# IHM.net
KiCad netlist of a schematic drawn in Altium Designer
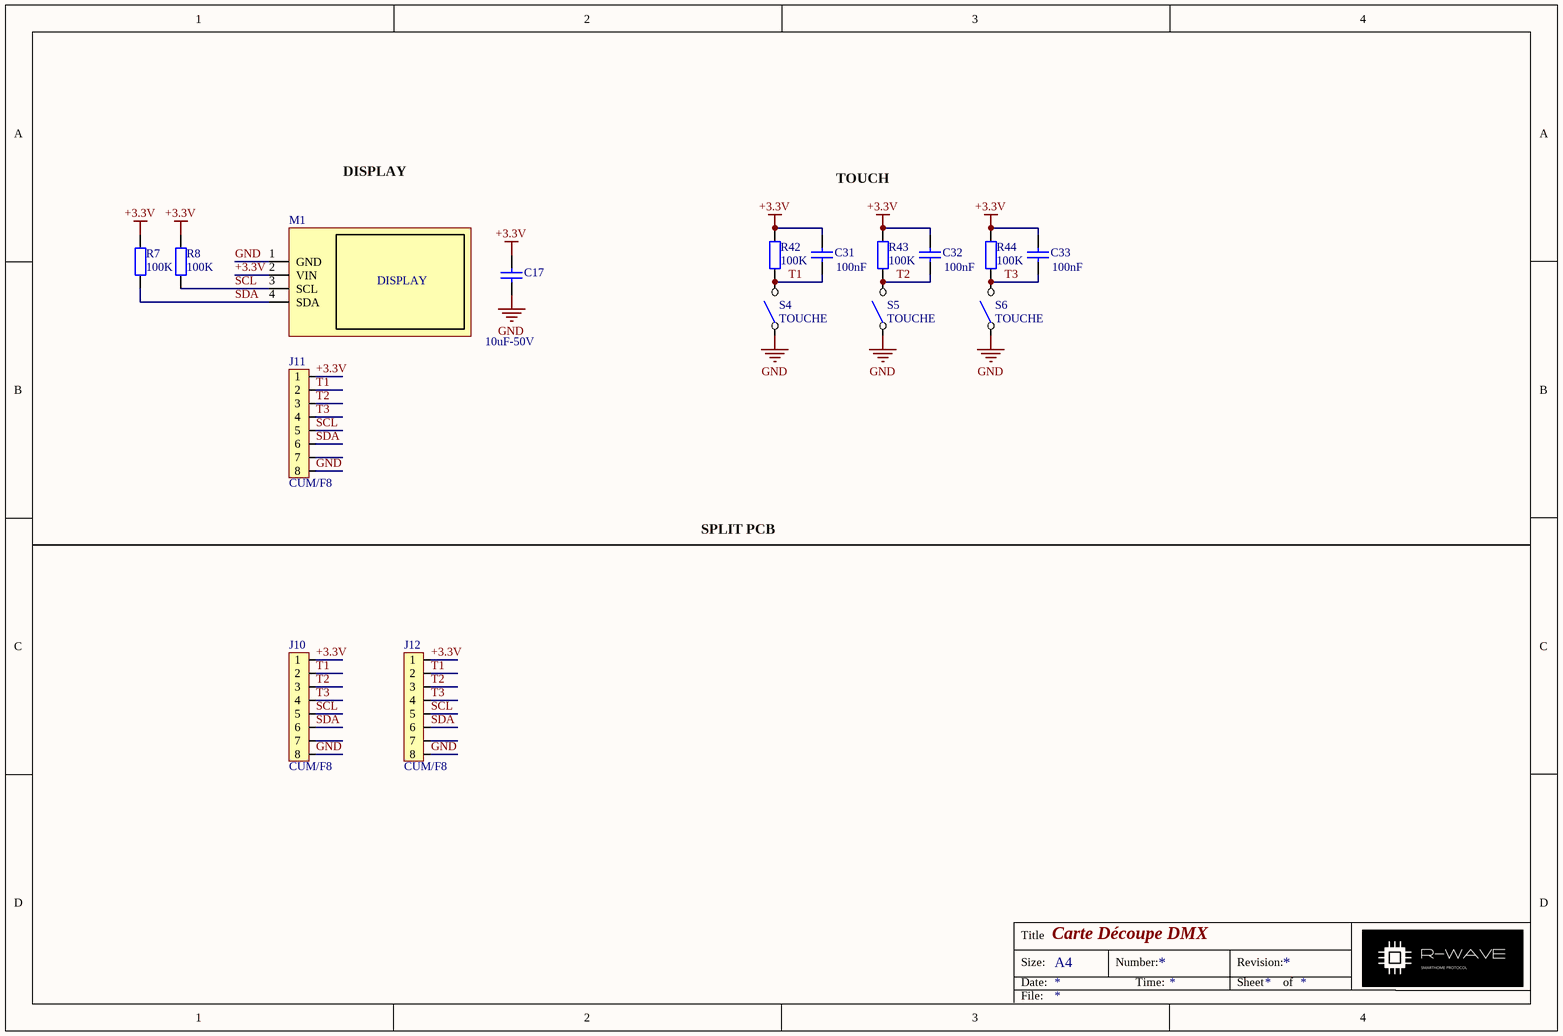
[diagram p0: IHM.SchDoc]

(export (version "E")
  (design (tool "Eeschema 10.0.6"))
  (components
    (comp (ref "C17")
      (value "10uF-50V")
      (footprint "C1206")
      (description "Capacitor")
      (libsource (lib "MyLibrary") (part "Cap"))
    )
    (comp (ref "C31")
      (value "100nF")
      (footprint "C0603")
      (description "Capacitor")
      (libsource (lib "MyLibrary") (part "Cap"))
    )
    (comp (ref "C32")
      (value "100nF")
      (footprint "C0603")
      (description "Capacitor")
      (libsource (lib "MyLibrary") (part "Cap"))
    )
    (comp (ref "C33")
      (value "100nF")
      (footprint "C0603")
      (description "Capacitor")
      (libsource (lib "MyLibrary") (part "Cap"))
    )
    (comp (ref "J10")
      (value "CUM/F8")
      (footprint "BARF-2X4")
      (description "connecteur 8 points")
      (libsource (lib "PROTEL") (part "CUM/F8"))
    )
    (comp (ref "J11")
      (value "CUM/F8")
      (footprint "BARF-2X4")
      (description "connecteur 8 points")
      (libsource (lib "PROTEL") (part "CUM/F8"))
    )
    (comp (ref "J12")
      (value "CUM/F8")
      (footprint "BARF-2X4")
      (description "connecteur 8 points")
      (libsource (lib "PROTEL") (part "CUM/F8"))
    )
    (comp (ref "M1")
      (value "~")
      (footprint "I2C_OLED_0.96")
      (description "I2C OLED 0.96\"")
      (libsource (lib "MyLibrary") (part "I2C-OLED-0.96"))
    )
    (comp (ref "R7")
      (value "100K")
      (footprint "R0603")
      (description "Thin Metal Film Resistor")
      (libsource (lib "MyLibrary") (part "Res"))
    )
    (comp (ref "R8")
      (value "100K")
      (footprint "R0603")
      (description "Thin Metal Film Resistor")
      (libsource (lib "MyLibrary") (part "Res"))
    )
    (comp (ref "R42")
      (value "100K")
      (footprint "R0603")
      (description "Thin Metal Film Resistor")
      (libsource (lib "MyLibrary") (part "Res"))
    )
    (comp (ref "R43")
      (value "100K")
      (footprint "R0603")
      (description "Thin Metal Film Resistor")
      (libsource (lib "MyLibrary") (part "Res"))
    )
    (comp (ref "R44")
      (value "100K")
      (footprint "R0603")
      (description "Thin Metal Film Resistor")
      (libsource (lib "MyLibrary") (part "Res"))
    )
    (comp (ref "S4")
      (value "TOUCHE")
      (footprint "INT-O")
      (description "Touche")
      (libsource (lib "PROTEL") (part "TOUCHE"))
    )
    (comp (ref "S5")
      (value "TOUCHE")
      (footprint "INT-O")
      (description "Touche")
      (libsource (lib "PROTEL") (part "TOUCHE"))
    )
    (comp (ref "S6")
      (value "TOUCHE")
      (footprint "INT-O")
      (description "Touche")
      (libsource (lib "PROTEL") (part "TOUCHE"))
    )
  )
  (nets
    (net (code "1") (name "+3.3V") (class "Default")
      (node (ref "C17") (pin "2") (pinfunction "2_2") (pintype "passive"))
      (node (ref "C31") (pin "2") (pinfunction "2_2") (pintype "passive"))
      (node (ref "C32") (pin "2") (pinfunction "2_2") (pintype "passive"))
      (node (ref "C33") (pin "2") (pinfunction "2_2") (pintype "passive"))
      (node (ref "J10") (pin "1") (pinfunction "1_1") (pintype "passive"))
      (node (ref "J11") (pin "1") (pinfunction "1_1") (pintype "passive"))
      (node (ref "J12") (pin "1") (pinfunction "1_1") (pintype "passive"))
      (node (ref "M1") (pin "2") (pinfunction "VIN_2") (pintype "power_in"))
      (node (ref "R42") (pin "2") (pinfunction "2_2") (pintype "passive"))
      (node (ref "R43") (pin "2") (pinfunction "2_2") (pintype "passive"))
      (node (ref "R44") (pin "2") (pinfunction "2_2") (pintype "passive"))
      (node (ref "R7") (pin "2") (pinfunction "2_2") (pintype "passive"))
      (node (ref "R8") (pin "2") (pinfunction "2_2") (pintype "passive"))
    )
    (net (code "2") (name "/SCL") (class "Default")
      (node (ref "J10") (pin "5") (pinfunction "5_5") (pintype "passive"))
      (node (ref "J11") (pin "5") (pinfunction "5_5") (pintype "passive"))
      (node (ref "J12") (pin "5") (pinfunction "5_5") (pintype "passive"))
      (node (ref "M1") (pin "3") (pinfunction "SCL_3") (pintype "power_in"))
      (node (ref "R8") (pin "1") (pinfunction "1_1") (pintype "passive"))
    )
    (net (code "3") (name "/SDA") (class "Default")
      (node (ref "J10") (pin "6") (pinfunction "6_6") (pintype "passive"))
      (node (ref "J11") (pin "6") (pinfunction "6_6") (pintype "passive"))
      (node (ref "J12") (pin "6") (pinfunction "6_6") (pintype "passive"))
      (node (ref "M1") (pin "4") (pinfunction "SDA_4") (pintype "power_in"))
      (node (ref "R7") (pin "1") (pinfunction "1_1") (pintype "passive"))
    )
    (net (code "4") (name "/T1") (class "Default")
      (node (ref "C31") (pin "1") (pinfunction "1_1") (pintype "passive"))
      (node (ref "J10") (pin "2") (pinfunction "2_2") (pintype "passive"))
      (node (ref "J11") (pin "2") (pinfunction "2_2") (pintype "passive"))
      (node (ref "J12") (pin "2") (pinfunction "2_2") (pintype "passive"))
      (node (ref "R42") (pin "1") (pinfunction "1_1") (pintype "passive"))
      (node (ref "S4") (pin "4") (pinfunction "4_4") (pintype "passive"))
    )
    (net (code "5") (name "/T2") (class "Default")
      (node (ref "C32") (pin "1") (pinfunction "1_1") (pintype "passive"))
      (node (ref "J10") (pin "3") (pinfunction "3_3") (pintype "passive"))
      (node (ref "J11") (pin "3") (pinfunction "3_3") (pintype "passive"))
      (node (ref "J12") (pin "3") (pinfunction "3_3") (pintype "passive"))
      (node (ref "R43") (pin "1") (pinfunction "1_1") (pintype "passive"))
      (node (ref "S5") (pin "4") (pinfunction "4_4") (pintype "passive"))
    )
    (net (code "6") (name "/T3") (class "Default")
      (node (ref "C33") (pin "1") (pinfunction "1_1") (pintype "passive"))
      (node (ref "J10") (pin "4") (pinfunction "4_4") (pintype "passive"))
      (node (ref "J11") (pin "4") (pinfunction "4_4") (pintype "passive"))
      (node (ref "J12") (pin "4") (pinfunction "4_4") (pintype "passive"))
      (node (ref "R44") (pin "1") (pinfunction "1_1") (pintype "passive"))
      (node (ref "S6") (pin "4") (pinfunction "4_4") (pintype "passive"))
    )
    (net (code "7") (name "GND") (class "Default")
      (node (ref "C17") (pin "1") (pinfunction "1_1") (pintype "passive"))
      (node (ref "J10") (pin "8") (pinfunction "8_8") (pintype "passive"))
      (node (ref "J11") (pin "8") (pinfunction "8_8") (pintype "passive"))
      (node (ref "J12") (pin "8") (pinfunction "8_8") (pintype "passive"))
      (node (ref "M1") (pin "1") (pinfunction "GND_1") (pintype "power_in"))
      (node (ref "S4") (pin "1") (pinfunction "1_1") (pintype "passive"))
      (node (ref "S5") (pin "1") (pinfunction "1_1") (pintype "passive"))
      (node (ref "S6") (pin "1") (pinfunction "1_1") (pintype "passive"))
    )
    (net (code "8") (name "unconnected-(J10-Pad7)") (class "Default")
      (node (ref "J10") (pin "7") (pinfunction "7_7") (pintype "passive"))
    )
    (net (code "9") (name "unconnected-(J11-Pad7)") (class "Default")
      (node (ref "J11") (pin "7") (pinfunction "7_7") (pintype "passive"))
    )
    (net (code "10") (name "unconnected-(J12-Pad7)") (class "Default")
      (node (ref "J12") (pin "7") (pinfunction "7_7") (pintype "passive"))
    )
  )
)
